# arBot-v1.net
KiCad netlist of a schematic drawn in EAGLE
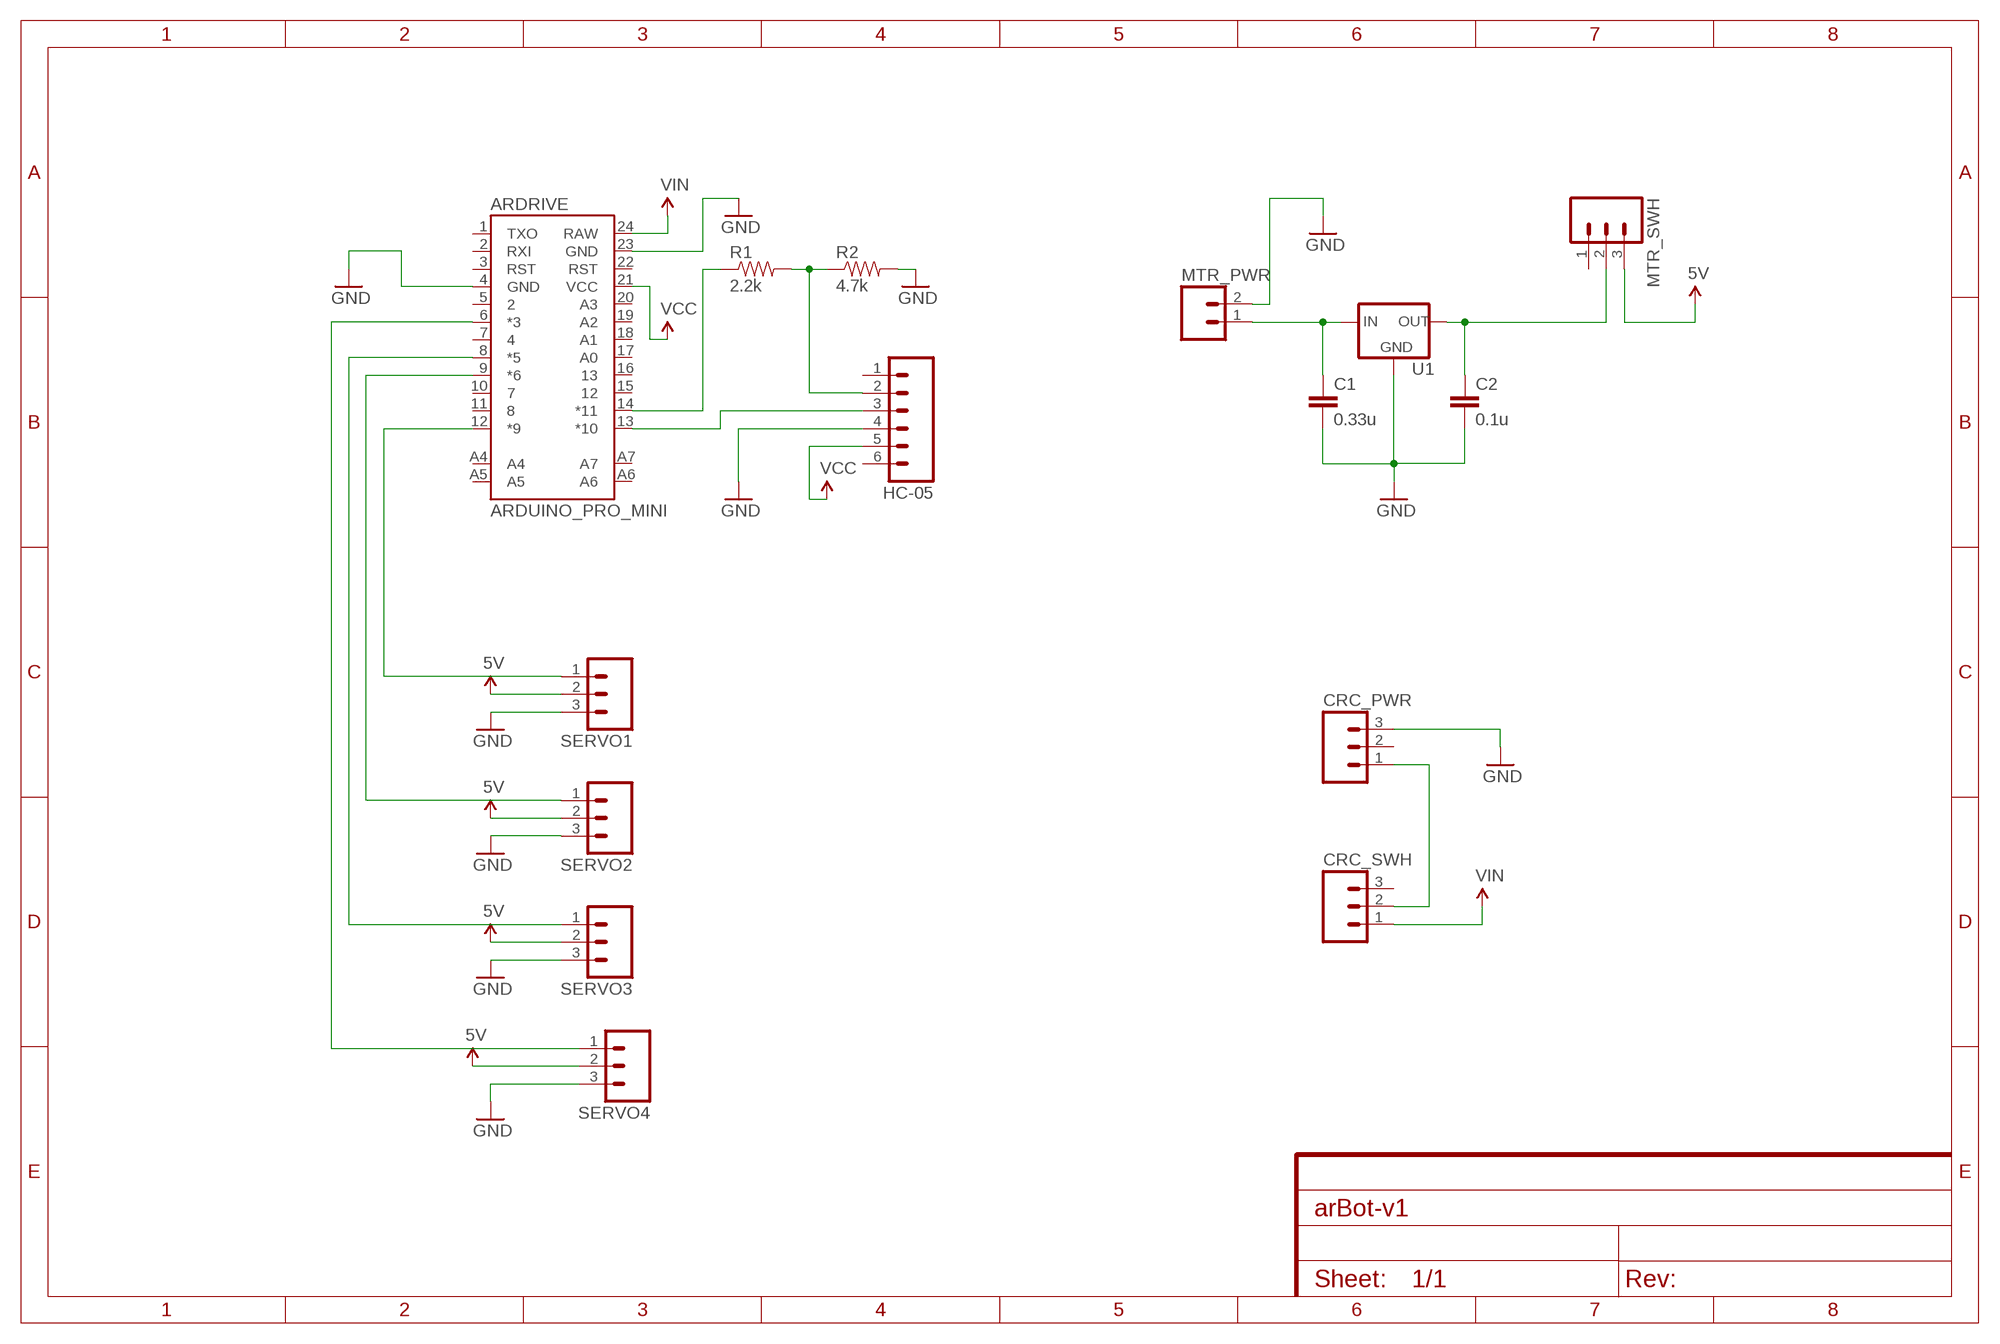
[diagram p0: schematic, sheet 1]

(export (version "E")
  (design (tool "Eeschema 10.0.6"))
  (components
    (comp (ref "ARDRIVE")
      (value "ARDUINO_PRO_MINI")
      (footprint "eagle-import:ARDUINO_PRO_MINI")
      (libsource (lib "eagle-import") (part "ARDUINO_PRO_MINI"))
    )
    (comp (ref "C1")
      (value "0.33u")
      (footprint "eagle-import:CAP-PTH-SMALL")
      (libsource (lib "eagle-import") (part "CAPPTH"))
    )
    (comp (ref "C2")
      (value "0.1u")
      (footprint "eagle-import:CAP-PTH-SMALL")
      (libsource (lib "eagle-import") (part "CAPPTH"))
    )
    (comp (ref "CRC_PWR")
      (value "M03LONGPADS")
      (footprint "eagle-import:1X03_LONGPADS")
      (libsource (lib "eagle-import") (part "M03LONGPADS"))
    )
    (comp (ref "CRC_SWH")
      (value "M03LOCK_LONGPADS")
      (footprint "eagle-import:1X03_LOCK_LONGPADS")
      (libsource (lib "eagle-import") (part "M03LOCK_LONGPADS"))
    )
    (comp (ref "HC-05")
      (value "M06LOCK_LONGPADS")
      (footprint "eagle-import:1X06_LOCK_LONGPADS")
      (libsource (lib "eagle-import") (part "M06LOCK_LONGPADS"))
    )
    (comp (ref "MTR_PWR")
      (value "M025MM")
      (footprint "eagle-import:SCREWTERMINAL-5MM-2")
      (libsource (lib "eagle-import") (part "M025MM"))
    )
    (comp (ref "MTR_SWH")
      (value "M03-SCREW-5MM")
      (footprint "eagle-import:SCREWTERMINAL-5MM-3")
      (libsource (lib "eagle-import") (part "M03-SCREW-5MM"))
    )
    (comp (ref "R1")
      (value "2.2k")
      (footprint "eagle-import:AXIAL-0.3-KIT")
      (libsource (lib "eagle-import") (part "RESISTORKIT"))
    )
    (comp (ref "R2")
      (value "4.7k")
      (footprint "eagle-import:AXIAL-0.3-KIT")
      (libsource (lib "eagle-import") (part "RESISTORKIT"))
    )
    (comp (ref "SERVO1")
      (value "M03LONGPADS")
      (footprint "eagle-import:1X03_LONGPADS")
      (libsource (lib "eagle-import") (part "M03LONGPADS"))
    )
    (comp (ref "SERVO2")
      (value "M03LONGPADS")
      (footprint "eagle-import:1X03_LONGPADS")
      (libsource (lib "eagle-import") (part "M03LONGPADS"))
    )
    (comp (ref "SERVO3")
      (value "M03LONGPADS")
      (footprint "eagle-import:1X03_LONGPADS")
      (libsource (lib "eagle-import") (part "M03LONGPADS"))
    )
    (comp (ref "SERVO4")
      (value "M03LONGPADS")
      (footprint "eagle-import:1X03_LONGPADS")
      (libsource (lib "eagle-import") (part "M03LONGPADS"))
    )
    (comp (ref "U1")
      (value "V_REG_78XX-TO-220")
      (footprint "eagle-import:TO-220-ALT")
      (libsource (lib "eagle-import") (part "V_REG_78XX-TO-220"))
    )
  )
  (nets
    (net (code "1") (name "5V") (class "Default")
      (node (ref "MTR_SWH") (pin "3") (pinfunction "3_3") (pintype "passive"))
      (node (ref "SERVO1") (pin "2") (pinfunction "2_2") (pintype "passive"))
      (node (ref "SERVO2") (pin "2") (pinfunction "2_2") (pintype "passive"))
      (node (ref "SERVO3") (pin "2") (pinfunction "2_2") (pintype "passive"))
      (node (ref "SERVO4") (pin "2") (pinfunction "2_2") (pintype "passive"))
    )
    (net (code "2") (name "GND") (class "Default")
      (node (ref "ARDRIVE") (pin "23") (pinfunction "GND_23") (pintype "bidirectional"))
      (node (ref "ARDRIVE") (pin "4") (pinfunction "GND_4") (pintype "bidirectional"))
      (node (ref "C1") (pin "2") (pinfunction "2_2") (pintype "passive"))
      (node (ref "C2") (pin "2") (pinfunction "2_2") (pintype "passive"))
      (node (ref "CRC_PWR") (pin "3") (pinfunction "3_3") (pintype "passive"))
      (node (ref "HC-05") (pin "4") (pinfunction "4_4") (pintype "passive"))
      (node (ref "MTR_PWR") (pin "2") (pinfunction "2_2") (pintype "passive"))
      (node (ref "R2") (pin "P$2") (pinfunction "2_P$2") (pintype "passive"))
      (node (ref "SERVO1") (pin "3") (pinfunction "3_3") (pintype "passive"))
      (node (ref "SERVO2") (pin "3") (pinfunction "3_3") (pintype "passive"))
      (node (ref "SERVO3") (pin "3") (pinfunction "3_3") (pintype "passive"))
      (node (ref "SERVO4") (pin "3") (pinfunction "3_3") (pintype "passive"))
      (node (ref "U1") (pin "GND") (pinfunction "GND_GND") (pintype "input"))
    )
    (net (code "3") (name "Net-(ARDRIVE-*3)") (class "Default")
      (node (ref "ARDRIVE") (pin "6") (pinfunction "*3_6") (pintype "bidirectional"))
      (node (ref "SERVO4") (pin "1") (pinfunction "1_1") (pintype "passive"))
    )
    (net (code "4") (name "Net-(ARDRIVE-*5)") (class "Default")
      (node (ref "ARDRIVE") (pin "8") (pinfunction "*5_8") (pintype "bidirectional"))
      (node (ref "SERVO3") (pin "1") (pinfunction "1_1") (pintype "passive"))
    )
    (net (code "5") (name "Net-(ARDRIVE-*6)") (class "Default")
      (node (ref "ARDRIVE") (pin "9") (pinfunction "*6_9") (pintype "bidirectional"))
      (node (ref "SERVO2") (pin "1") (pinfunction "1_1") (pintype "passive"))
    )
    (net (code "6") (name "Net-(ARDRIVE-*9)") (class "Default")
      (node (ref "ARDRIVE") (pin "12") (pinfunction "*9_12") (pintype "bidirectional"))
      (node (ref "SERVO1") (pin "1") (pinfunction "1_1") (pintype "passive"))
    )
    (net (code "7") (name "Net-(ARDRIVE-*10)") (class "Default")
      (node (ref "ARDRIVE") (pin "13") (pinfunction "*10_13") (pintype "bidirectional"))
      (node (ref "HC-05") (pin "3") (pinfunction "3_3") (pintype "passive"))
    )
    (net (code "8") (name "Net-(ARDRIVE-*11)") (class "Default")
      (node (ref "ARDRIVE") (pin "14") (pinfunction "*11_14") (pintype "bidirectional"))
      (node (ref "R1") (pin "P$1") (pinfunction "1_P$1") (pintype "passive"))
    )
    (net (code "9") (name "Net-(C1-Pad1)") (class "Default")
      (node (ref "C1") (pin "1") (pinfunction "1_1") (pintype "passive"))
      (node (ref "MTR_PWR") (pin "1") (pinfunction "1_1") (pintype "passive"))
      (node (ref "U1") (pin "IN") (pinfunction "IN_IN") (pintype "input"))
    )
    (net (code "10") (name "Net-(C2-Pad1)") (class "Default")
      (node (ref "C2") (pin "1") (pinfunction "1_1") (pintype "passive"))
      (node (ref "MTR_SWH") (pin "2") (pinfunction "2_2") (pintype "passive"))
      (node (ref "U1") (pin "OUT") (pinfunction "OUT_OUT") (pintype "passive"))
    )
    (net (code "11") (name "Net-(CRC_PWR-Pad1)") (class "Default")
      (node (ref "CRC_PWR") (pin "1") (pinfunction "1_1") (pintype "passive"))
      (node (ref "CRC_SWH") (pin "2") (pinfunction "2_2") (pintype "passive"))
    )
    (net (code "12") (name "Net-(R1-2)") (class "Default")
      (node (ref "HC-05") (pin "2") (pinfunction "2_2") (pintype "passive"))
      (node (ref "R1") (pin "P$2") (pinfunction "2_P$2") (pintype "passive"))
      (node (ref "R2") (pin "P$1") (pinfunction "1_P$1") (pintype "passive"))
    )
    (net (code "13") (name "VCC") (class "Default")
      (node (ref "ARDRIVE") (pin "21") (pinfunction "VCC_21") (pintype "bidirectional"))
      (node (ref "HC-05") (pin "5") (pinfunction "5_5") (pintype "passive"))
    )
    (net (code "14") (name "VIN") (class "Default")
      (node (ref "ARDRIVE") (pin "24") (pinfunction "RAW_24") (pintype "bidirectional"))
      (node (ref "CRC_SWH") (pin "1") (pinfunction "1_1") (pintype "passive"))
    )
    (net (code "15") (name "unconnected-(ARDRIVE-2-Pad5)") (class "Default")
      (node (ref "ARDRIVE") (pin "5") (pinfunction "2_5") (pintype "bidirectional"))
    )
    (net (code "16") (name "unconnected-(ARDRIVE-4-Pad7)") (class "Default")
      (node (ref "ARDRIVE") (pin "7") (pinfunction "4_7") (pintype "bidirectional"))
    )
    (net (code "17") (name "unconnected-(ARDRIVE-7-Pad10)") (class "Default")
      (node (ref "ARDRIVE") (pin "10") (pinfunction "7_10") (pintype "bidirectional"))
    )
    (net (code "18") (name "unconnected-(ARDRIVE-8-Pad11)") (class "Default")
      (node (ref "ARDRIVE") (pin "11") (pinfunction "8_11") (pintype "bidirectional"))
    )
    (net (code "19") (name "unconnected-(ARDRIVE-12-Pad15)") (class "Default")
      (node (ref "ARDRIVE") (pin "15") (pinfunction "12_15") (pintype "bidirectional"))
    )
    (net (code "20") (name "unconnected-(ARDRIVE-13-Pad16)") (class "Default")
      (node (ref "ARDRIVE") (pin "16") (pinfunction "13_16") (pintype "bidirectional"))
    )
    (net (code "21") (name "unconnected-(ARDRIVE-A0-Pad17)") (class "Default")
      (node (ref "ARDRIVE") (pin "17") (pinfunction "A0_17") (pintype "bidirectional"))
    )
    (net (code "22") (name "unconnected-(ARDRIVE-A1-Pad18)") (class "Default")
      (node (ref "ARDRIVE") (pin "18") (pinfunction "A1_18") (pintype "bidirectional"))
    )
    (net (code "23") (name "unconnected-(ARDRIVE-A2-Pad19)") (class "Default")
      (node (ref "ARDRIVE") (pin "19") (pinfunction "A2_19") (pintype "bidirectional"))
    )
    (net (code "24") (name "unconnected-(ARDRIVE-A3-Pad20)") (class "Default")
      (node (ref "ARDRIVE") (pin "20") (pinfunction "A3_20") (pintype "bidirectional"))
    )
    (net (code "25") (name "unconnected-(ARDRIVE-PadA4)") (class "Default")
      (node (ref "ARDRIVE") (pin "A4") (pinfunction "A4_A4") (pintype "bidirectional"))
    )
    (net (code "26") (name "unconnected-(ARDRIVE-PadA5)") (class "Default")
      (node (ref "ARDRIVE") (pin "A5") (pinfunction "A5_A5") (pintype "bidirectional"))
    )
    (net (code "27") (name "unconnected-(ARDRIVE-PadA6)") (class "Default")
      (node (ref "ARDRIVE") (pin "A6") (pinfunction "A6_A6") (pintype "bidirectional"))
    )
    (net (code "28") (name "unconnected-(ARDRIVE-PadA7)") (class "Default")
      (node (ref "ARDRIVE") (pin "A7") (pinfunction "A7_A7") (pintype "bidirectional"))
    )
    (net (code "29") (name "unconnected-(ARDRIVE-RST-Pad3)") (class "Default")
      (node (ref "ARDRIVE") (pin "3") (pinfunction "RST_3") (pintype "bidirectional"))
    )
    (net (code "30") (name "unconnected-(ARDRIVE-RST-Pad22)") (class "Default")
      (node (ref "ARDRIVE") (pin "22") (pinfunction "RST_22") (pintype "bidirectional"))
    )
    (net (code "31") (name "unconnected-(ARDRIVE-RXI-Pad2)") (class "Default")
      (node (ref "ARDRIVE") (pin "2") (pinfunction "RXI_2") (pintype "bidirectional"))
    )
    (net (code "32") (name "unconnected-(ARDRIVE-TXO-Pad1)") (class "Default")
      (node (ref "ARDRIVE") (pin "1") (pinfunction "TXO_1") (pintype "bidirectional"))
    )
    (net (code "33") (name "unconnected-(CRC_PWR-Pad2)") (class "Default")
      (node (ref "CRC_PWR") (pin "2") (pinfunction "2_2") (pintype "passive"))
    )
    (net (code "34") (name "unconnected-(CRC_SWH-Pad3)") (class "Default")
      (node (ref "CRC_SWH") (pin "3") (pinfunction "3_3") (pintype "passive"))
    )
    (net (code "35") (name "unconnected-(HC-05-Pad1)") (class "Default")
      (node (ref "HC-05") (pin "1") (pinfunction "1_1") (pintype "passive"))
    )
    (net (code "36") (name "unconnected-(HC-05-Pad6)") (class "Default")
      (node (ref "HC-05") (pin "6") (pinfunction "6_6") (pintype "passive"))
    )
    (net (code "37") (name "unconnected-(MTR_SWH-Pad1)") (class "Default")
      (node (ref "MTR_SWH") (pin "1") (pinfunction "1_1") (pintype "passive"))
    )
  )
)
